# Sheet1.net
KiCad netlist of a schematic drawn in Altium Designer
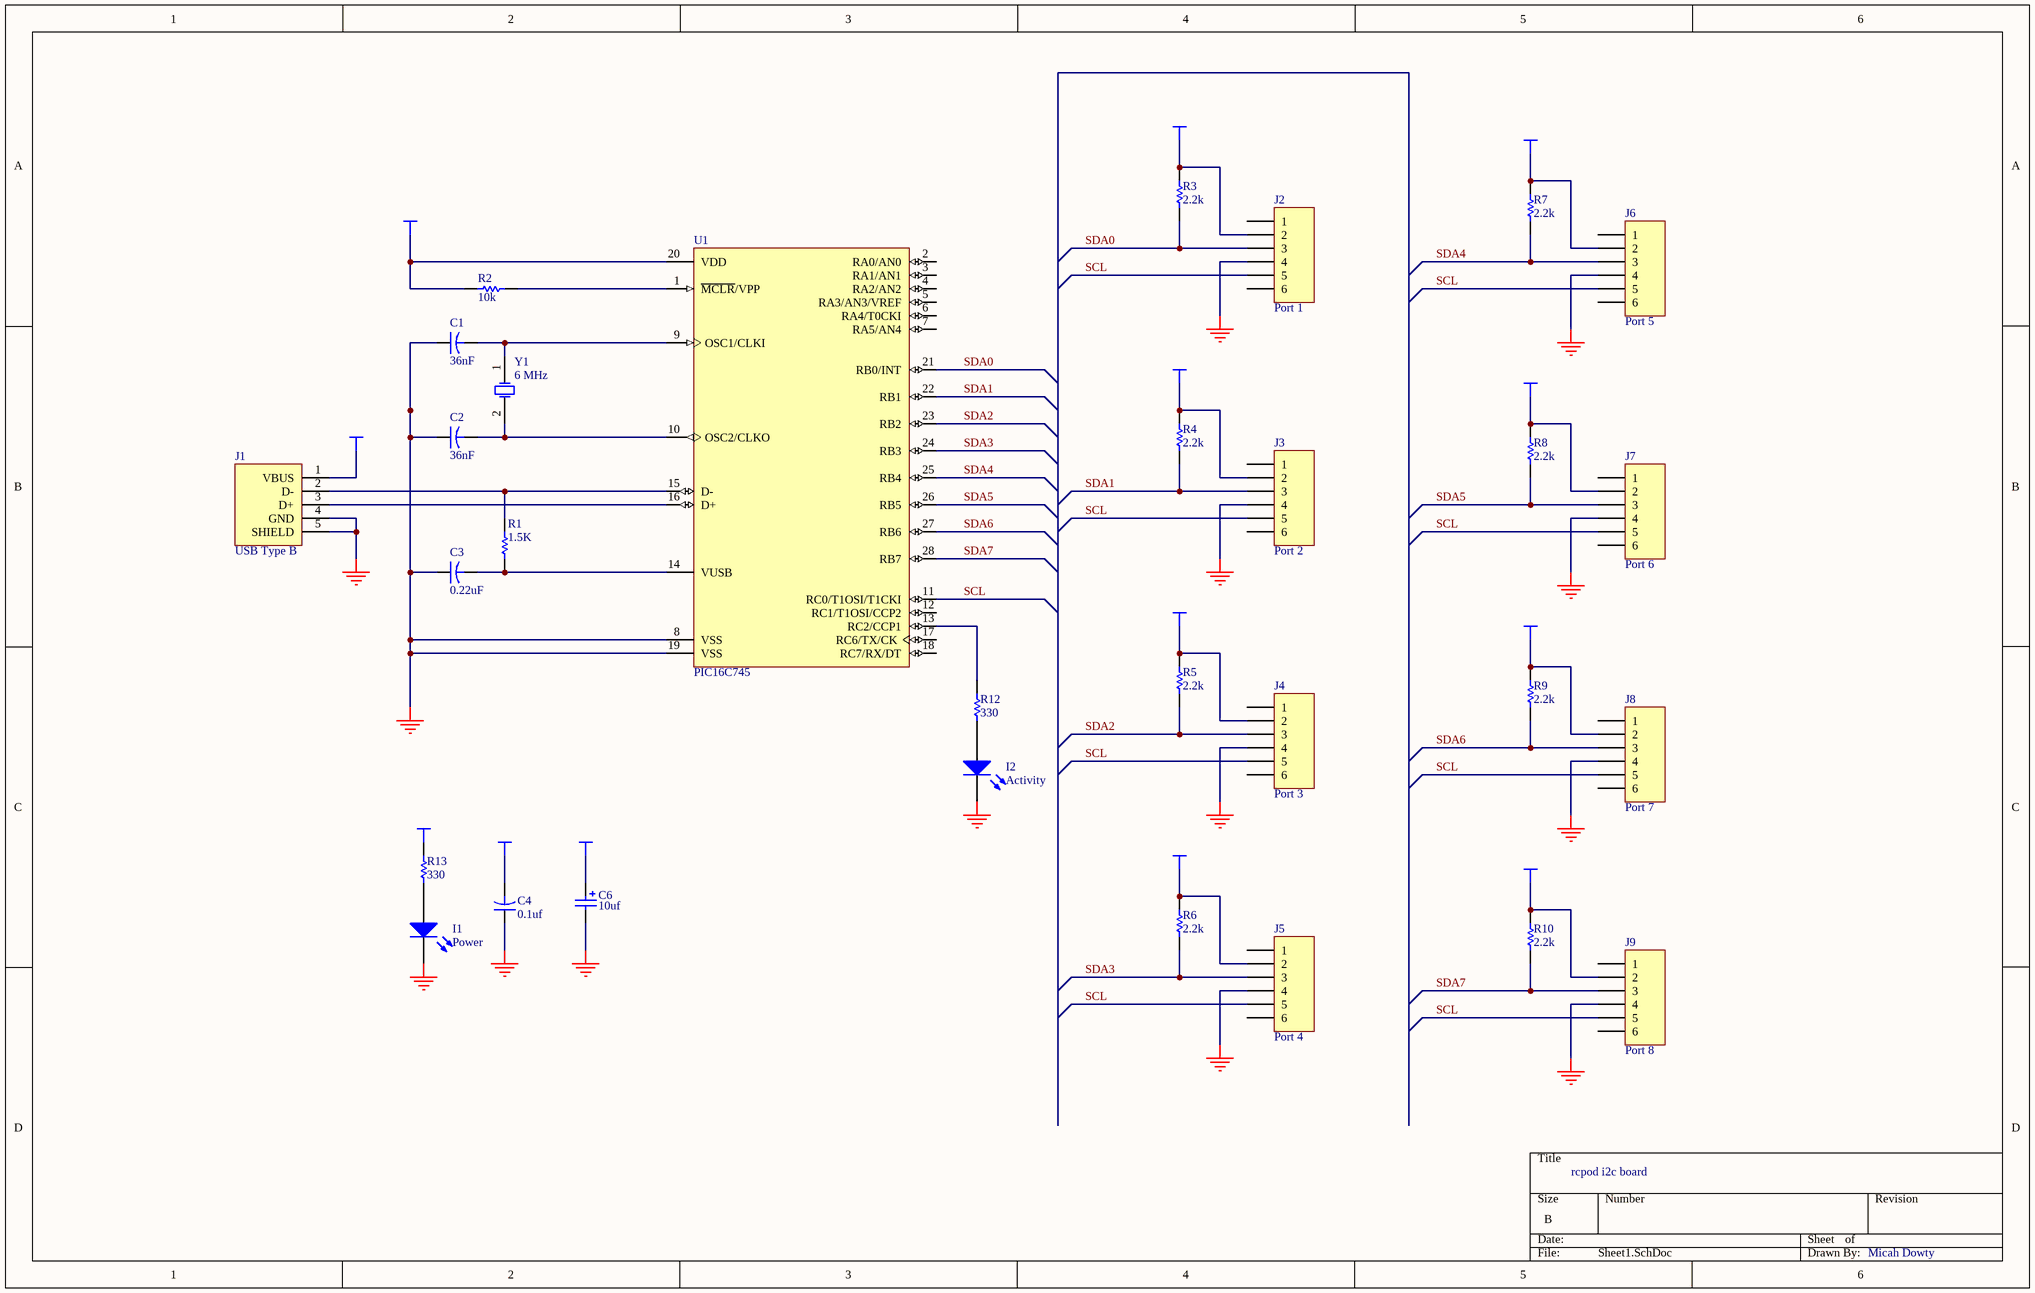
[diagram p0: Sheet1.SchDoc]

(export (version "E")
  (design (tool "Eeschema 10.0.6"))
  (components
    (comp (ref "C1")
      (value "Cap2")
      (footprint "CAPR5-4X5")
      (description "Capacitor")
      (fields
        (field (name "MANUFACTURER") "Generic Components")
        (field (name "ALTIUM_VALUE") "36nF")
        (field (name "PUBLISHER") "Altium Limited")
      )
      (libsource (lib "Miscellaneous Devices") (part "Cap2"))
    )
    (comp (ref "C2")
      (value "Cap2")
      (footprint "CAPR5-4X5")
      (description "Capacitor")
      (fields
        (field (name "MANUFACTURER") "Generic Components")
        (field (name "ALTIUM_VALUE") "36nF")
        (field (name "PUBLISHER") "Altium Limited")
      )
      (libsource (lib "Miscellaneous Devices") (part "Cap2"))
    )
    (comp (ref "C3")
      (value "0.22uF")
      (footprint "CAPR5-4X5")
      (description "Capacitor")
      (fields (field (name "MANUFACTURER") "Generic Components") (field (name "PUBLISHER") "Altium Limited"))
      (libsource (lib "Miscellaneous Devices") (part "Cap2"))
    )
    (comp (ref "C4")
      (value "0.1uf")
      (footprint "CAPR5-4X5")
      (description "Capacitor")
      (fields (field (name "MANUFACTURER") "Generic Components") (field (name "PUBLISHER") "Altium Limited"))
      (libsource (lib "Miscellaneous Devices") (part "Cap2"))
    )
    (comp (ref "C6")
      (value "Cap Pol1")
      (footprint "CAP-EE-1")
      (description "Polarized Capacitor (Radial)")
      (fields
        (field (name "MANUFACTURER") "Generic Components")
        (field (name "ALTIUM_VALUE") "10uf")
        (field (name "PUBLISHER") "Altium Limited")
      )
      (libsource (lib "Miscellaneous Devices") (part "Cap Pol1"))
    )
    (comp (ref "I1")
      (value "Power")
      (footprint "LED5MM")
      (description "Typical INFRARED GaAs LED")
      (fields (field (name "MANUFACTURER") "Generic Components") (field (name "PUBLISHER") "Altium Limited"))
      (libsource (lib "Miscellaneous Devices") (part "LED0"))
    )
    (comp (ref "I2")
      (value "Activity")
      (footprint "LED5MM")
      (description "Typical INFRARED GaAs LED")
      (fields (field (name "MANUFACTURER") "Generic Components") (field (name "PUBLISHER") "Altium Limited"))
      (libsource (lib "Miscellaneous Devices") (part "LED0"))
    )
    (comp (ref "J1")
      (value "USB")
      (footprint "USB-TYPEB")
      (description "Header, 4-Pin")
      (fields (field (name "MANUFACTURER") "Generic Components") (field (name "PUBLISHER") "Altium Limited"))
      (libsource (lib "parts") (part "USB Type B"))
    )
    (comp (ref "J2")
      (value "Port 1")
      (footprint "RJ11")
      (description "Header, 6-Pin")
      (fields (field (name "MANUFACTURER") "Generic Components") (field (name "PUBLISHER") "Altium Limited"))
      (libsource (lib "Miscellaneous Connectors") (part "Header 6"))
    )
    (comp (ref "J3")
      (value "Port 2")
      (footprint "RJ11")
      (description "Header, 6-Pin")
      (fields (field (name "MANUFACTURER") "Generic Components") (field (name "PUBLISHER") "Altium Limited"))
      (libsource (lib "Miscellaneous Connectors") (part "Header 6"))
    )
    (comp (ref "J4")
      (value "Port 3")
      (footprint "RJ11")
      (description "Header, 6-Pin")
      (fields (field (name "MANUFACTURER") "Generic Components") (field (name "PUBLISHER") "Altium Limited"))
      (libsource (lib "Miscellaneous Connectors") (part "Header 6"))
    )
    (comp (ref "J5")
      (value "Port 4")
      (footprint "RJ11")
      (description "Header, 6-Pin")
      (fields (field (name "MANUFACTURER") "Generic Components") (field (name "PUBLISHER") "Altium Limited"))
      (libsource (lib "Miscellaneous Connectors") (part "Header 6"))
    )
    (comp (ref "J6")
      (value "Port 5")
      (footprint "RJ11")
      (description "Header, 6-Pin")
      (fields (field (name "MANUFACTURER") "Generic Components") (field (name "PUBLISHER") "Altium Limited"))
      (libsource (lib "Miscellaneous Connectors") (part "Header 6"))
    )
    (comp (ref "J7")
      (value "Port 6")
      (footprint "RJ11")
      (description "Header, 6-Pin")
      (fields (field (name "MANUFACTURER") "Generic Components") (field (name "PUBLISHER") "Altium Limited"))
      (libsource (lib "Miscellaneous Connectors") (part "Header 6"))
    )
    (comp (ref "J8")
      (value "Port 7")
      (footprint "RJ11")
      (description "Header, 6-Pin")
      (fields (field (name "MANUFACTURER") "Generic Components") (field (name "PUBLISHER") "Altium Limited"))
      (libsource (lib "Miscellaneous Connectors") (part "Header 6"))
    )
    (comp (ref "J9")
      (value "Port 8")
      (footprint "RJ11")
      (description "Header, 6-Pin")
      (fields (field (name "MANUFACTURER") "Generic Components") (field (name "PUBLISHER") "Altium Limited"))
      (libsource (lib "Miscellaneous Connectors") (part "Header 6"))
    )
    (comp (ref "R1")
      (value "Res1")
      (footprint "AXIAL-0.3")
      (description "Resistor")
      (fields
        (field (name "MANUFACTURER") "Generic Components")
        (field (name "ALTIUM_VALUE") "1.5K")
        (field (name "PUBLISHER") "Altium Limited")
      )
      (libsource (lib "Miscellaneous Devices") (part "Res1"))
    )
    (comp (ref "R2")
      (value "Res1")
      (footprint "AXIAL-0.3")
      (description "Resistor")
      (fields
        (field (name "MANUFACTURER") "Generic Components")
        (field (name "ALTIUM_VALUE") "10k")
        (field (name "PUBLISHER") "Altium Limited")
      )
      (libsource (lib "Miscellaneous Devices") (part "Res1"))
    )
    (comp (ref "R3")
      (value "Res1")
      (footprint "AXIAL-0.3")
      (description "Resistor")
      (fields
        (field (name "MANUFACTURER") "Generic Components")
        (field (name "ALTIUM_VALUE") "2.2k")
        (field (name "PUBLISHER") "Altium Limited")
      )
      (libsource (lib "Miscellaneous Devices") (part "Res1"))
    )
    (comp (ref "R4")
      (value "Res1")
      (footprint "AXIAL-0.3")
      (description "Resistor")
      (fields
        (field (name "MANUFACTURER") "Generic Components")
        (field (name "ALTIUM_VALUE") "2.2k")
        (field (name "PUBLISHER") "Altium Limited")
      )
      (libsource (lib "Miscellaneous Devices") (part "Res1"))
    )
    (comp (ref "R5")
      (value "Res1")
      (footprint "AXIAL-0.3")
      (description "Resistor")
      (fields
        (field (name "MANUFACTURER") "Generic Components")
        (field (name "ALTIUM_VALUE") "2.2k")
        (field (name "PUBLISHER") "Altium Limited")
      )
      (libsource (lib "Miscellaneous Devices") (part "Res1"))
    )
    (comp (ref "R6")
      (value "Res1")
      (footprint "AXIAL-0.3")
      (description "Resistor")
      (fields
        (field (name "MANUFACTURER") "Generic Components")
        (field (name "ALTIUM_VALUE") "2.2k")
        (field (name "PUBLISHER") "Altium Limited")
      )
      (libsource (lib "Miscellaneous Devices") (part "Res1"))
    )
    (comp (ref "R7")
      (value "Res1")
      (footprint "AXIAL-0.3")
      (description "Resistor")
      (fields
        (field (name "MANUFACTURER") "Generic Components")
        (field (name "ALTIUM_VALUE") "2.2k")
        (field (name "PUBLISHER") "Altium Limited")
      )
      (libsource (lib "Miscellaneous Devices") (part "Res1"))
    )
    (comp (ref "R8")
      (value "Res1")
      (footprint "AXIAL-0.3")
      (description "Resistor")
      (fields
        (field (name "MANUFACTURER") "Generic Components")
        (field (name "ALTIUM_VALUE") "2.2k")
        (field (name "PUBLISHER") "Altium Limited")
      )
      (libsource (lib "Miscellaneous Devices") (part "Res1"))
    )
    (comp (ref "R9")
      (value "Res1")
      (footprint "AXIAL-0.3")
      (description "Resistor")
      (fields
        (field (name "MANUFACTURER") "Generic Components")
        (field (name "ALTIUM_VALUE") "2.2k")
        (field (name "PUBLISHER") "Altium Limited")
      )
      (libsource (lib "Miscellaneous Devices") (part "Res1"))
    )
    (comp (ref "R10")
      (value "Res1")
      (footprint "AXIAL-0.3")
      (description "Resistor")
      (fields
        (field (name "MANUFACTURER") "Generic Components")
        (field (name "ALTIUM_VALUE") "2.2k")
        (field (name "PUBLISHER") "Altium Limited")
      )
      (libsource (lib "Miscellaneous Devices") (part "Res1"))
    )
    (comp (ref "R12")
      (value "Res1")
      (footprint "AXIAL-0.3")
      (description "Resistor")
      (fields
        (field (name "MANUFACTURER") "Generic Components")
        (field (name "ALTIUM_VALUE") "330")
        (field (name "PUBLISHER") "Altium Limited")
      )
      (libsource (lib "Miscellaneous Devices") (part "Res1"))
    )
    (comp (ref "R13")
      (value "Res1")
      (footprint "AXIAL-0.3")
      (description "Resistor")
      (fields
        (field (name "MANUFACTURER") "Generic Components")
        (field (name "ALTIUM_VALUE") "330")
        (field (name "PUBLISHER") "Altium Limited")
      )
      (libsource (lib "Miscellaneous Devices") (part "Res1"))
    )
    (comp (ref "U1")
      (value "~")
      (footprint "DIP-28")
      (description "EPROM-Based 8-Bit CMOS Microcontroller with USB")
      (fields (field (name "MANUFACTURER") "Microchip"))
      (libsource (lib "parts") (part "PIC16C745"))
    )
    (comp (ref "Y1")
      (value "6 MHz")
      (footprint "BCY-W2/E4.7")
      (description "Crystal Oscillator")
      (fields (field (name "MANUFACTURER") "Generic Components") (field (name "PUBLISHER") "Altium Limited"))
      (libsource (lib "Miscellaneous Devices") (part "XTAL"))
    )
  )
  (nets
    (net (code "1") (name "/SCL") (class "Default")
      (node (ref "J2") (pin "5") (pinfunction "5_5") (pintype "passive"))
      (node (ref "J3") (pin "5") (pinfunction "5_5") (pintype "passive"))
      (node (ref "J4") (pin "5") (pinfunction "5_5") (pintype "passive"))
      (node (ref "J5") (pin "5") (pinfunction "5_5") (pintype "passive"))
      (node (ref "J6") (pin "5") (pinfunction "5_5") (pintype "passive"))
      (node (ref "J7") (pin "5") (pinfunction "5_5") (pintype "passive"))
      (node (ref "J8") (pin "5") (pinfunction "5_5") (pintype "passive"))
      (node (ref "J9") (pin "5") (pinfunction "5_5") (pintype "passive"))
      (node (ref "U1") (pin "11") (pinfunction "RC0/T1OSI/T1CKI_11") (pintype "bidirectional"))
    )
    (net (code "2") (name "/SDA0") (class "Default")
      (node (ref "J2") (pin "3") (pinfunction "3_3") (pintype "passive"))
      (node (ref "R3") (pin "2") (pinfunction "2_2") (pintype "passive"))
      (node (ref "U1") (pin "21") (pinfunction "RB0/INT_21") (pintype "bidirectional"))
    )
    (net (code "3") (name "/SDA1") (class "Default")
      (node (ref "J3") (pin "3") (pinfunction "3_3") (pintype "passive"))
      (node (ref "R4") (pin "2") (pinfunction "2_2") (pintype "passive"))
      (node (ref "U1") (pin "22") (pinfunction "RB1_22") (pintype "bidirectional"))
    )
    (net (code "4") (name "/SDA2") (class "Default")
      (node (ref "J4") (pin "3") (pinfunction "3_3") (pintype "passive"))
      (node (ref "R5") (pin "2") (pinfunction "2_2") (pintype "passive"))
      (node (ref "U1") (pin "23") (pinfunction "RB2_23") (pintype "bidirectional"))
    )
    (net (code "5") (name "/SDA3") (class "Default")
      (node (ref "J5") (pin "3") (pinfunction "3_3") (pintype "passive"))
      (node (ref "R6") (pin "2") (pinfunction "2_2") (pintype "passive"))
      (node (ref "U1") (pin "24") (pinfunction "RB3_24") (pintype "bidirectional"))
    )
    (net (code "6") (name "/SDA4") (class "Default")
      (node (ref "J6") (pin "3") (pinfunction "3_3") (pintype "passive"))
      (node (ref "R7") (pin "2") (pinfunction "2_2") (pintype "passive"))
      (node (ref "U1") (pin "25") (pinfunction "RB4_25") (pintype "bidirectional"))
    )
    (net (code "7") (name "/SDA5") (class "Default")
      (node (ref "J7") (pin "3") (pinfunction "3_3") (pintype "passive"))
      (node (ref "R8") (pin "2") (pinfunction "2_2") (pintype "passive"))
      (node (ref "U1") (pin "26") (pinfunction "RB5_26") (pintype "bidirectional"))
    )
    (net (code "8") (name "/SDA6") (class "Default")
      (node (ref "J8") (pin "3") (pinfunction "3_3") (pintype "passive"))
      (node (ref "R9") (pin "2") (pinfunction "2_2") (pintype "passive"))
      (node (ref "U1") (pin "27") (pinfunction "RB6_27") (pintype "bidirectional"))
    )
    (net (code "9") (name "/SDA7") (class "Default")
      (node (ref "J9") (pin "3") (pinfunction "3_3") (pintype "passive"))
      (node (ref "R10") (pin "2") (pinfunction "2_2") (pintype "passive"))
      (node (ref "U1") (pin "28") (pinfunction "RB7_28") (pintype "bidirectional"))
    )
    (net (code "10") (name "GND") (class "Default")
      (node (ref "C1") (pin "1") (pinfunction "1_1") (pintype "passive"))
      (node (ref "C2") (pin "1") (pinfunction "1_1") (pintype "passive"))
      (node (ref "C3") (pin "1") (pinfunction "1_1") (pintype "passive"))
      (node (ref "C4") (pin "1") (pinfunction "1_1") (pintype "passive"))
      (node (ref "C6") (pin "2") (pinfunction "2_2") (pintype "passive"))
      (node (ref "I1") (pin "2") (pinfunction "K_2") (pintype "passive"))
      (node (ref "I2") (pin "2") (pinfunction "K_2") (pintype "passive"))
      (node (ref "J1") (pin "4") (pinfunction "GND_4") (pintype "passive"))
      (node (ref "J1") (pin "5") (pinfunction "SHIELD_5") (pintype "power_in"))
      (node (ref "J2") (pin "4") (pinfunction "4_4") (pintype "passive"))
      (node (ref "J3") (pin "4") (pinfunction "4_4") (pintype "passive"))
      (node (ref "J4") (pin "4") (pinfunction "4_4") (pintype "passive"))
      (node (ref "J5") (pin "4") (pinfunction "4_4") (pintype "passive"))
      (node (ref "J6") (pin "4") (pinfunction "4_4") (pintype "passive"))
      (node (ref "J7") (pin "4") (pinfunction "4_4") (pintype "passive"))
      (node (ref "J8") (pin "4") (pinfunction "4_4") (pintype "passive"))
      (node (ref "J9") (pin "4") (pinfunction "4_4") (pintype "passive"))
      (node (ref "U1") (pin "19") (pinfunction "VSS_19") (pintype "power_in"))
      (node (ref "U1") (pin "8") (pinfunction "VSS_8") (pintype "power_in"))
    )
    (net (code "11") (name "Net-(I1-A)") (class "Default")
      (node (ref "I1") (pin "1") (pinfunction "A_1") (pintype "passive"))
      (node (ref "R13") (pin "2") (pinfunction "2_2") (pintype "passive"))
    )
    (net (code "12") (name "Net-(I2-A)") (class "Default")
      (node (ref "I2") (pin "1") (pinfunction "A_1") (pintype "passive"))
      (node (ref "R12") (pin "2") (pinfunction "2_2") (pintype "passive"))
    )
    (net (code "13") (name "Net-(J1-D+)") (class "Default")
      (node (ref "J1") (pin "3") (pinfunction "D+_3") (pintype "passive"))
      (node (ref "U1") (pin "16") (pinfunction "D+_16") (pintype "bidirectional"))
    )
    (net (code "14") (name "Net-(J1-D-)") (class "Default")
      (node (ref "J1") (pin "2") (pinfunction "D-_2") (pintype "passive"))
      (node (ref "R1") (pin "2") (pinfunction "2_2") (pintype "passive"))
      (node (ref "U1") (pin "15") (pinfunction "D-_15") (pintype "bidirectional"))
    )
    (net (code "15") (name "Net-(U1-OSC1{slash}CLKI)") (class "Default")
      (node (ref "C1") (pin "2") (pinfunction "2_2") (pintype "passive"))
      (node (ref "U1") (pin "9") (pinfunction "OSC1/CLKI_9") (pintype "input"))
      (node (ref "Y1") (pin "1") (pinfunction "OSC1_1") (pintype "passive"))
    )
    (net (code "16") (name "Net-(U1-OSC2{slash}CLKO)") (class "Default")
      (node (ref "C2") (pin "2") (pinfunction "2_2") (pintype "passive"))
      (node (ref "U1") (pin "10") (pinfunction "OSC2/CLKO_10") (pintype "output"))
      (node (ref "Y1") (pin "2") (pinfunction "OSC2_2") (pintype "passive"))
    )
    (net (code "17") (name "Net-(U1-RC2{slash}CCP1)") (class "Default")
      (node (ref "R12") (pin "1") (pinfunction "1_1") (pintype "passive"))
      (node (ref "U1") (pin "13") (pinfunction "RC2/CCP1_13") (pintype "bidirectional"))
    )
    (net (code "18") (name "Net-(U1-VUSB)") (class "Default")
      (node (ref "C3") (pin "2") (pinfunction "2_2") (pintype "passive"))
      (node (ref "R1") (pin "1") (pinfunction "1_1") (pintype "passive"))
      (node (ref "U1") (pin "14") (pinfunction "VUSB_14") (pintype "power_in"))
    )
    (net (code "19") (name "Net-(U1-~{MCLR}{slash}VPP)") (class "Default")
      (node (ref "R2") (pin "1") (pinfunction "1_1") (pintype "passive"))
      (node (ref "U1") (pin "1") (pinfunction "~{MCLR}/VPP_1") (pintype "input"))
    )
    (net (code "20") (name "VCC") (class "Default")
      (node (ref "C4") (pin "2") (pinfunction "2_2") (pintype "passive"))
      (node (ref "C6") (pin "1") (pinfunction "1_1") (pintype "passive"))
      (node (ref "J1") (pin "1") (pinfunction "VBUS_1") (pintype "passive"))
      (node (ref "J2") (pin "2") (pinfunction "2_2") (pintype "passive"))
      (node (ref "J3") (pin "2") (pinfunction "2_2") (pintype "passive"))
      (node (ref "J4") (pin "2") (pinfunction "2_2") (pintype "passive"))
      (node (ref "J5") (pin "2") (pinfunction "2_2") (pintype "passive"))
      (node (ref "J6") (pin "2") (pinfunction "2_2") (pintype "passive"))
      (node (ref "J7") (pin "2") (pinfunction "2_2") (pintype "passive"))
      (node (ref "J8") (pin "2") (pinfunction "2_2") (pintype "passive"))
      (node (ref "J9") (pin "2") (pinfunction "2_2") (pintype "passive"))
      (node (ref "R10") (pin "1") (pinfunction "1_1") (pintype "passive"))
      (node (ref "R13") (pin "1") (pinfunction "1_1") (pintype "passive"))
      (node (ref "R2") (pin "2") (pinfunction "2_2") (pintype "passive"))
      (node (ref "R3") (pin "1") (pinfunction "1_1") (pintype "passive"))
      (node (ref "R4") (pin "1") (pinfunction "1_1") (pintype "passive"))
      (node (ref "R5") (pin "1") (pinfunction "1_1") (pintype "passive"))
      (node (ref "R6") (pin "1") (pinfunction "1_1") (pintype "passive"))
      (node (ref "R7") (pin "1") (pinfunction "1_1") (pintype "passive"))
      (node (ref "R8") (pin "1") (pinfunction "1_1") (pintype "passive"))
      (node (ref "R9") (pin "1") (pinfunction "1_1") (pintype "passive"))
      (node (ref "U1") (pin "20") (pinfunction "VDD_20") (pintype "power_in"))
    )
    (net (code "21") (name "unconnected-(J2-Pad1)") (class "Default")
      (node (ref "J2") (pin "1") (pinfunction "1_1") (pintype "passive"))
    )
    (net (code "22") (name "unconnected-(J2-Pad6)") (class "Default")
      (node (ref "J2") (pin "6") (pinfunction "6_6") (pintype "passive"))
    )
    (net (code "23") (name "unconnected-(J3-Pad1)") (class "Default")
      (node (ref "J3") (pin "1") (pinfunction "1_1") (pintype "passive"))
    )
    (net (code "24") (name "unconnected-(J3-Pad6)") (class "Default")
      (node (ref "J3") (pin "6") (pinfunction "6_6") (pintype "passive"))
    )
    (net (code "25") (name "unconnected-(J4-Pad1)") (class "Default")
      (node (ref "J4") (pin "1") (pinfunction "1_1") (pintype "passive"))
    )
    (net (code "26") (name "unconnected-(J4-Pad6)") (class "Default")
      (node (ref "J4") (pin "6") (pinfunction "6_6") (pintype "passive"))
    )
    (net (code "27") (name "unconnected-(J5-Pad1)") (class "Default")
      (node (ref "J5") (pin "1") (pinfunction "1_1") (pintype "passive"))
    )
    (net (code "28") (name "unconnected-(J5-Pad6)") (class "Default")
      (node (ref "J5") (pin "6") (pinfunction "6_6") (pintype "passive"))
    )
    (net (code "29") (name "unconnected-(J6-Pad1)") (class "Default")
      (node (ref "J6") (pin "1") (pinfunction "1_1") (pintype "passive"))
    )
    (net (code "30") (name "unconnected-(J6-Pad6)") (class "Default")
      (node (ref "J6") (pin "6") (pinfunction "6_6") (pintype "passive"))
    )
    (net (code "31") (name "unconnected-(J7-Pad1)") (class "Default")
      (node (ref "J7") (pin "1") (pinfunction "1_1") (pintype "passive"))
    )
    (net (code "32") (name "unconnected-(J7-Pad6)") (class "Default")
      (node (ref "J7") (pin "6") (pinfunction "6_6") (pintype "passive"))
    )
    (net (code "33") (name "unconnected-(J8-Pad1)") (class "Default")
      (node (ref "J8") (pin "1") (pinfunction "1_1") (pintype "passive"))
    )
    (net (code "34") (name "unconnected-(J8-Pad6)") (class "Default")
      (node (ref "J8") (pin "6") (pinfunction "6_6") (pintype "passive"))
    )
    (net (code "35") (name "unconnected-(J9-Pad1)") (class "Default")
      (node (ref "J9") (pin "1") (pinfunction "1_1") (pintype "passive"))
    )
    (net (code "36") (name "unconnected-(J9-Pad6)") (class "Default")
      (node (ref "J9") (pin "6") (pinfunction "6_6") (pintype "passive"))
    )
    (net (code "37") (name "unconnected-(U1-RA0{slash}AN0-Pad2)") (class "Default")
      (node (ref "U1") (pin "2") (pinfunction "RA0/AN0_2") (pintype "bidirectional"))
    )
    (net (code "38") (name "unconnected-(U1-RA1{slash}AN1-Pad3)") (class "Default")
      (node (ref "U1") (pin "3") (pinfunction "RA1/AN1_3") (pintype "bidirectional"))
    )
    (net (code "39") (name "unconnected-(U1-RA2{slash}AN2-Pad4)") (class "Default")
      (node (ref "U1") (pin "4") (pinfunction "RA2/AN2_4") (pintype "bidirectional"))
    )
    (net (code "40") (name "unconnected-(U1-RA3{slash}AN3{slash}VREF-Pad5)") (class "Default")
      (node (ref "U1") (pin "5") (pinfunction "RA3/AN3/VREF_5") (pintype "bidirectional"))
    )
    (net (code "41") (name "unconnected-(U1-RA4{slash}T0CKI-Pad6)") (class "Default")
      (node (ref "U1") (pin "6") (pinfunction "RA4/T0CKI_6") (pintype "bidirectional"))
    )
    (net (code "42") (name "unconnected-(U1-RA5{slash}AN4-Pad7)") (class "Default")
      (node (ref "U1") (pin "7") (pinfunction "RA5/AN4_7") (pintype "bidirectional"))
    )
    (net (code "43") (name "unconnected-(U1-RC1{slash}T1OSI{slash}CCP2-Pad12)") (class "Default")
      (node (ref "U1") (pin "12") (pinfunction "RC1/T1OSI/CCP2_12") (pintype "bidirectional"))
    )
    (net (code "44") (name "unconnected-(U1-RC6{slash}TX{slash}CK-Pad17)") (class "Default")
      (node (ref "U1") (pin "17") (pinfunction "RC6/TX/CK_17") (pintype "bidirectional"))
    )
    (net (code "45") (name "unconnected-(U1-RC7{slash}RX{slash}DT-Pad18)") (class "Default")
      (node (ref "U1") (pin "18") (pinfunction "RC7/RX/DT_18") (pintype "bidirectional"))
    )
  )
)
